# WSTL18P2.net
KiCad netlist of a schematic drawn in EAGLE
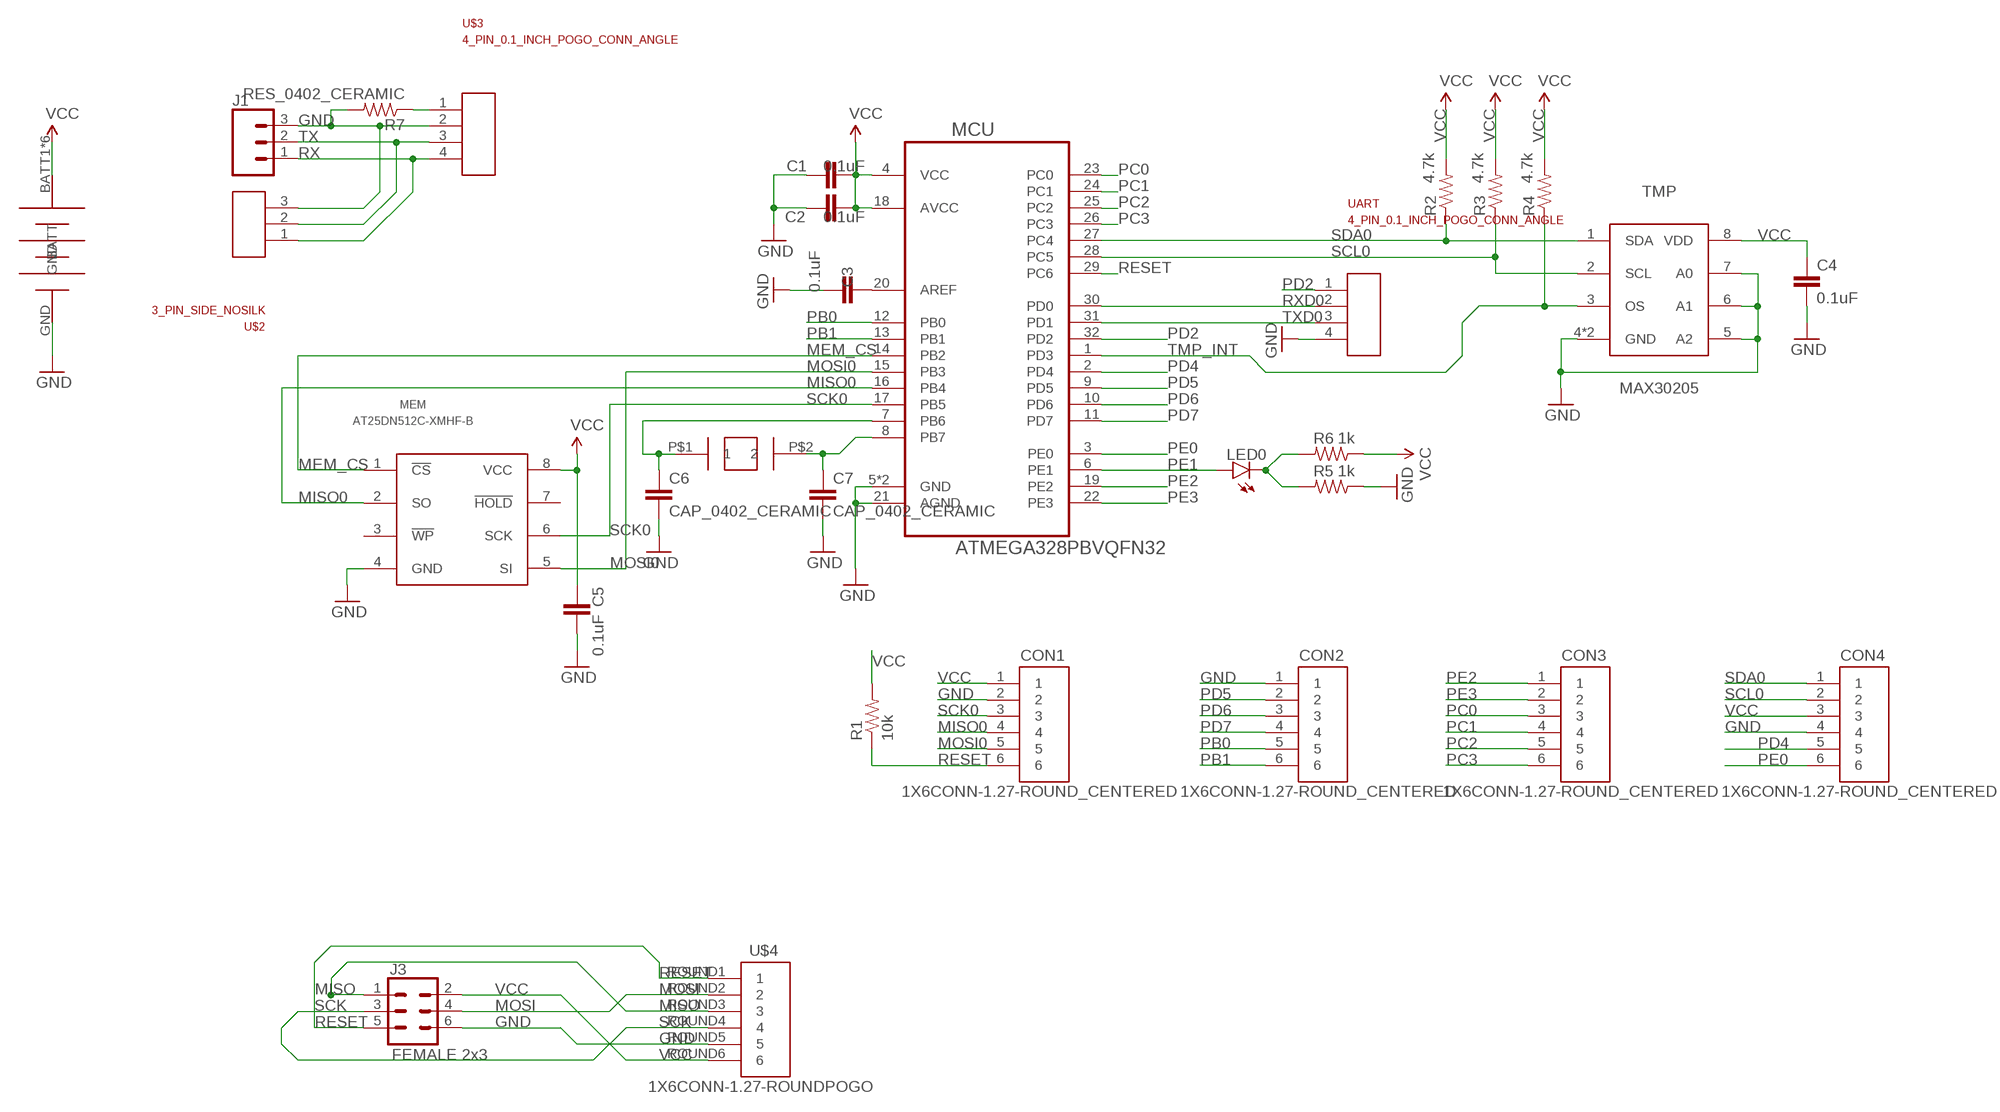
[diagram p0: schematic, sheet 1]

(export (version "E")
  (design (tool "Eeschema 10.0.6"))
  (components
    (comp (ref "C1")
      (value "0.1uF")
      (footprint "eagle-import:SMD_0402")
      (libsource (lib "eagle-import") (part "CAP_0402"))
    )
    (comp (ref "C2")
      (value "0.1uF")
      (footprint "eagle-import:SMD_0402")
      (libsource (lib "eagle-import") (part "CAP_0402"))
    )
    (comp (ref "C3")
      (value "0.1uF")
      (footprint "eagle-import:SMD_0402")
      (libsource (lib "eagle-import") (part "CAP_0402"))
    )
    (comp (ref "C4")
      (value "0.1uF")
      (footprint "eagle-import:CAP_0402")
      (libsource (lib "eagle-import") (part "CAP_0402_CERAMIC"))
    )
    (comp (ref "C5")
      (value "0.1uF")
      (footprint "eagle-import:CAP_0402")
      (libsource (lib "eagle-import") (part "CAP_0402_CERAMIC"))
    )
    (comp (ref "C6")
      (value "CAP_0402_CERAMIC")
      (footprint "eagle-import:CAP_0402")
      (libsource (lib "eagle-import") (part "CAP_0402_CERAMIC"))
    )
    (comp (ref "C7")
      (value "CAP_0402_CERAMIC")
      (footprint "eagle-import:CAP_0402")
      (libsource (lib "eagle-import") (part "CAP_0402_CERAMIC"))
    )
    (comp (ref "CON1")
      (value "1X6CONN-1.27-ROUND_CENTERED")
      (footprint "eagle-import:1X6_1.27_ROUND_CENTERED")
      (libsource (lib "eagle-import") (part "1X6CONN-1.27-ROUND_CENTERED"))
    )
    (comp (ref "CON2")
      (value "1X6CONN-1.27-ROUND_CENTERED")
      (footprint "eagle-import:1X6_1.27_ROUND_CENTERED")
      (libsource (lib "eagle-import") (part "1X6CONN-1.27-ROUND_CENTERED"))
    )
    (comp (ref "CON3")
      (value "1X6CONN-1.27-ROUND_CENTERED")
      (footprint "eagle-import:1X6_1.27_ROUND_CENTERED")
      (libsource (lib "eagle-import") (part "1X6CONN-1.27-ROUND_CENTERED"))
    )
    (comp (ref "CON4")
      (value "1X6CONN-1.27-ROUND_CENTERED")
      (footprint "eagle-import:1X6_1.27_ROUND_CENTERED")
      (libsource (lib "eagle-import") (part "1X6CONN-1.27-ROUND_CENTERED"))
    )
    (comp (ref "J1")
      (value "CONN_03")
      (footprint "eagle-import:1X03")
      (libsource (lib "eagle-import") (part "CONN_03"))
    )
    (comp (ref "J3")
      (value "FEMALE 2x3")
      (footprint "eagle-import:2X3")
      (libsource (lib "eagle-import") (part "CONN_03X2FEMALE"))
    )
    (comp (ref "LED0")
      (value "LED_0402")
      (footprint "eagle-import:LED_0402")
      (libsource (lib "eagle-import") (part "LED_0402"))
    )
    (comp (ref "MCU")
      (value "ATMEGA328PBVQFN32")
      (footprint "eagle-import:ATMEGA328PB_VFQFN32")
      (libsource (lib "eagle-import") (part "ATMEGA328PBVQFN32"))
    )
    (comp (ref "MEM")
      (value "AT25DN512C-XMHF-B")
      (footprint "eagle-import:TSSSOP-8")
      (libsource (lib "eagle-import") (part "AT25DN512C-XMHF-B"))
    )
    (comp (ref "R1")
      (value "10k")
      (footprint "eagle-import:RES_0402")
      (libsource (lib "eagle-import") (part "RES_0402_CERAMIC"))
    )
    (comp (ref "R2")
      (value "4.7k")
      (footprint "eagle-import:RES_0402")
      (libsource (lib "eagle-import") (part "RES_0402_CERAMIC"))
    )
    (comp (ref "R3")
      (value "4.7k")
      (footprint "eagle-import:RES_0402")
      (libsource (lib "eagle-import") (part "RES_0402_CERAMIC"))
    )
    (comp (ref "R4")
      (value "4.7k")
      (footprint "eagle-import:RES_0402")
      (libsource (lib "eagle-import") (part "RES_0402_CERAMIC"))
    )
    (comp (ref "R5")
      (value "1k")
      (footprint "eagle-import:RES_0402")
      (libsource (lib "eagle-import") (part "RES_0402_CERAMIC"))
    )
    (comp (ref "R6")
      (value "1k")
      (footprint "eagle-import:RES_0402")
      (libsource (lib "eagle-import") (part "RES_0402_CERAMIC"))
    )
    (comp (ref "R7")
      (value "RES_0402_CERAMIC")
      (footprint "eagle-import:RES_0402")
      (libsource (lib "eagle-import") (part "RES_0402_CERAMIC"))
    )
    (comp (ref "T1")
      (value "ABS07AIG")
      (footprint "eagle-import:ABS07AIG")
      (libsource (lib "eagle-import") (part "ABS07AIG"))
    )
    (comp (ref "TMP")
      (value "MAX30205")
      (footprint "eagle-import:MAX30205_TDFN8")
      (libsource (lib "eagle-import") (part "MAX30205"))
    )
    (comp (ref "U$1")
      (value "LINX-CR2032-BAT-HLD-M-THM")
      (footprint "eagle-import:CR2032-LINX-M-THM")
      (libsource (lib "eagle-import") (part "LINX-CR2032-BAT-HLD-M-THM"))
    )
    (comp (ref "U$2")
      (value "3_PIN_SIDE_NOSILK")
      (footprint "eagle-import:3PIN_SIDE_0.1_INCH_NOSILK")
      (libsource (lib "eagle-import") (part "3_PIN_SIDE_NOSILK"))
    )
    (comp (ref "U$3")
      (value "4_PIN_0.1_INCH_POGO_CONN_ANGLE")
      (footprint "eagle-import:4_PIN_0.1INCH_POGO_PADS_ANGLE")
      (libsource (lib "eagle-import") (part "4_PIN_0.1_INCH_POGO_CONN_ANGLE"))
    )
    (comp (ref "U$4")
      (value "1X6CONN-1.27-ROUNDPOGO")
      (footprint "eagle-import:1X6_1.27_SIDEPOGO")
      (libsource (lib "eagle-import") (part "1X6CONN-1.27-ROUNDPOGO"))
    )
    (comp (ref "UART")
      (value "4_PIN_0.1_INCH_POGO_CONN_ANGLE")
      (footprint "eagle-import:4_PIN_0.1INCH_POGO_PADS_ANGLE")
      (libsource (lib "eagle-import") (part "4_PIN_0.1_INCH_POGO_CONN_ANGLE"))
    )
  )
  (nets
    (net (code "1") (name "/MEM_CS") (class "Default")
      (node (ref "MCU") (pin "14") (pinfunction "PB2_14") (pintype "bidirectional"))
      (node (ref "MEM") (pin "1") (pinfunction "~{CS}_1") (pintype "bidirectional"))
    )
    (net (code "2") (name "/MISO") (class "Default")
      (node (ref "J3") (pin "1") (pinfunction "1_1") (pintype "bidirectional"))
      (node (ref "U$4") (pin "ROUND3") (pinfunction "3_ROUND3") (pintype "bidirectional"))
    )
    (net (code "3") (name "/MISO0") (class "Default")
      (node (ref "CON1") (pin "4") (pinfunction "4_4") (pintype "bidirectional"))
      (node (ref "MCU") (pin "16") (pinfunction "PB4_16") (pintype "bidirectional"))
      (node (ref "MEM") (pin "2") (pinfunction "SO_2") (pintype "bidirectional"))
    )
    (net (code "4") (name "/MOSI") (class "Default")
      (node (ref "J3") (pin "4") (pinfunction "4_4") (pintype "bidirectional"))
      (node (ref "U$4") (pin "ROUND2") (pinfunction "2_ROUND2") (pintype "bidirectional"))
    )
    (net (code "5") (name "/MOSI0") (class "Default")
      (node (ref "CON1") (pin "5") (pinfunction "5_5") (pintype "bidirectional"))
      (node (ref "MCU") (pin "15") (pinfunction "PB3_15") (pintype "bidirectional"))
      (node (ref "MEM") (pin "5") (pinfunction "SI_5") (pintype "bidirectional"))
    )
    (net (code "6") (name "/PB0") (class "Default")
      (node (ref "CON2") (pin "5") (pinfunction "5_5") (pintype "bidirectional"))
      (node (ref "MCU") (pin "12") (pinfunction "PB0_12") (pintype "bidirectional"))
    )
    (net (code "7") (name "/PB1") (class "Default")
      (node (ref "CON2") (pin "6") (pinfunction "6_6") (pintype "bidirectional"))
      (node (ref "MCU") (pin "13") (pinfunction "PB1_13") (pintype "bidirectional"))
    )
    (net (code "8") (name "/PC0") (class "Default")
      (node (ref "CON3") (pin "3") (pinfunction "3_3") (pintype "bidirectional"))
      (node (ref "MCU") (pin "23") (pinfunction "PC0_23") (pintype "bidirectional"))
    )
    (net (code "9") (name "/PC1") (class "Default")
      (node (ref "CON3") (pin "4") (pinfunction "4_4") (pintype "bidirectional"))
      (node (ref "MCU") (pin "24") (pinfunction "PC1_24") (pintype "bidirectional"))
    )
    (net (code "10") (name "/PC2") (class "Default")
      (node (ref "CON3") (pin "5") (pinfunction "5_5") (pintype "bidirectional"))
      (node (ref "MCU") (pin "25") (pinfunction "PC2_25") (pintype "bidirectional"))
    )
    (net (code "11") (name "/PC3") (class "Default")
      (node (ref "CON3") (pin "6") (pinfunction "6_6") (pintype "bidirectional"))
      (node (ref "MCU") (pin "26") (pinfunction "PC3_26") (pintype "bidirectional"))
    )
    (net (code "12") (name "/PD2") (class "Default")
      (node (ref "MCU") (pin "32") (pinfunction "PD2_32") (pintype "bidirectional"))
      (node (ref "UART") (pin "1") (pinfunction "1_1") (pintype "bidirectional"))
    )
    (net (code "13") (name "/PD4") (class "Default")
      (node (ref "CON4") (pin "5") (pinfunction "5_5") (pintype "bidirectional"))
      (node (ref "MCU") (pin "2") (pinfunction "PD4_2") (pintype "bidirectional"))
    )
    (net (code "14") (name "/PD5") (class "Default")
      (node (ref "CON2") (pin "2") (pinfunction "2_2") (pintype "bidirectional"))
      (node (ref "MCU") (pin "9") (pinfunction "PD5_9") (pintype "bidirectional"))
    )
    (net (code "15") (name "/PD6") (class "Default")
      (node (ref "CON2") (pin "3") (pinfunction "3_3") (pintype "bidirectional"))
      (node (ref "MCU") (pin "10") (pinfunction "PD6_10") (pintype "bidirectional"))
    )
    (net (code "16") (name "/PD7") (class "Default")
      (node (ref "CON2") (pin "4") (pinfunction "4_4") (pintype "bidirectional"))
      (node (ref "MCU") (pin "11") (pinfunction "PD7_11") (pintype "bidirectional"))
    )
    (net (code "17") (name "/PE0") (class "Default")
      (node (ref "CON4") (pin "6") (pinfunction "6_6") (pintype "bidirectional"))
      (node (ref "MCU") (pin "3") (pinfunction "PE0_3") (pintype "bidirectional"))
    )
    (net (code "18") (name "/PE1") (class "Default")
      (node (ref "LED0") (pin "ANODE") (pinfunction "A_ANODE") (pintype "passive"))
      (node (ref "MCU") (pin "6") (pinfunction "PE1_6") (pintype "bidirectional"))
    )
    (net (code "19") (name "/PE2") (class "Default")
      (node (ref "CON3") (pin "1") (pinfunction "1_1") (pintype "bidirectional"))
      (node (ref "MCU") (pin "19") (pinfunction "PE2_19") (pintype "bidirectional"))
    )
    (net (code "20") (name "/PE3") (class "Default")
      (node (ref "CON3") (pin "2") (pinfunction "2_2") (pintype "bidirectional"))
      (node (ref "MCU") (pin "22") (pinfunction "PE3_22") (pintype "bidirectional"))
    )
    (net (code "21") (name "/RESET") (class "Default")
      (node (ref "CON1") (pin "6") (pinfunction "6_6") (pintype "bidirectional"))
      (node (ref "J3") (pin "5") (pinfunction "5_5") (pintype "bidirectional"))
      (node (ref "MCU") (pin "29") (pinfunction "PC6_29") (pintype "bidirectional"))
      (node (ref "R1") (pin "2") (pinfunction "2_2") (pintype "passive"))
      (node (ref "U$4") (pin "ROUND1") (pinfunction "1_ROUND1") (pintype "bidirectional"))
    )
    (net (code "22") (name "/RX") (class "Default")
      (node (ref "J1") (pin "1") (pinfunction "1_1") (pintype "passive"))
      (node (ref "U$2") (pin "1") (pinfunction "1_1") (pintype "bidirectional"))
      (node (ref "U$3") (pin "4") (pinfunction "4_4") (pintype "bidirectional"))
    )
    (net (code "23") (name "/RXD0") (class "Default")
      (node (ref "MCU") (pin "30") (pinfunction "PD0_30") (pintype "bidirectional"))
      (node (ref "UART") (pin "2") (pinfunction "2_2") (pintype "bidirectional"))
    )
    (net (code "24") (name "/SCK") (class "Default")
      (node (ref "J3") (pin "3") (pinfunction "3_3") (pintype "bidirectional"))
      (node (ref "U$4") (pin "ROUND4") (pinfunction "4_ROUND4") (pintype "bidirectional"))
    )
    (net (code "25") (name "/SCK0") (class "Default")
      (node (ref "CON1") (pin "3") (pinfunction "3_3") (pintype "bidirectional"))
      (node (ref "MCU") (pin "17") (pinfunction "PB5_17") (pintype "bidirectional"))
      (node (ref "MEM") (pin "6") (pinfunction "SCK_6") (pintype "bidirectional"))
    )
    (net (code "26") (name "/SCL0") (class "Default")
      (node (ref "CON4") (pin "2") (pinfunction "2_2") (pintype "bidirectional"))
      (node (ref "MCU") (pin "28") (pinfunction "PC5_28") (pintype "bidirectional"))
      (node (ref "R3") (pin "2") (pinfunction "2_2") (pintype "passive"))
      (node (ref "TMP") (pin "2") (pinfunction "SCL_2") (pintype "bidirectional"))
    )
    (net (code "27") (name "/SDA0") (class "Default")
      (node (ref "CON4") (pin "1") (pinfunction "1_1") (pintype "bidirectional"))
      (node (ref "MCU") (pin "27") (pinfunction "PC4_27") (pintype "bidirectional"))
      (node (ref "R2") (pin "2") (pinfunction "2_2") (pintype "passive"))
      (node (ref "TMP") (pin "1") (pinfunction "SDA_1") (pintype "bidirectional"))
    )
    (net (code "28") (name "/TMP_INT") (class "Default")
      (node (ref "MCU") (pin "1") (pinfunction "PD3_1") (pintype "bidirectional"))
      (node (ref "R4") (pin "2") (pinfunction "2_2") (pintype "passive"))
      (node (ref "TMP") (pin "3") (pinfunction "OS_3") (pintype "bidirectional"))
    )
    (net (code "29") (name "/TX") (class "Default")
      (node (ref "J1") (pin "2") (pinfunction "2_2") (pintype "passive"))
      (node (ref "U$2") (pin "2") (pinfunction "2_2") (pintype "bidirectional"))
      (node (ref "U$3") (pin "3") (pinfunction "3_3") (pintype "bidirectional"))
    )
    (net (code "30") (name "/TXD0") (class "Default")
      (node (ref "MCU") (pin "31") (pinfunction "PD1_31") (pintype "bidirectional"))
      (node (ref "UART") (pin "3") (pinfunction "3_3") (pintype "bidirectional"))
    )
    (net (code "31") (name "GND") (class "Default")
      (node (ref "C1") (pin "2") (pinfunction "2_2") (pintype "bidirectional"))
      (node (ref "C2") (pin "2") (pinfunction "2_2") (pintype "bidirectional"))
      (node (ref "C3") (pin "2") (pinfunction "2_2") (pintype "bidirectional"))
      (node (ref "C4") (pin "2") (pinfunction "2_2") (pintype "passive"))
      (node (ref "C5") (pin "2") (pinfunction "2_2") (pintype "passive"))
      (node (ref "C6") (pin "2") (pinfunction "2_2") (pintype "passive"))
      (node (ref "C7") (pin "2") (pinfunction "2_2") (pintype "passive"))
      (node (ref "CON1") (pin "2") (pinfunction "2_2") (pintype "bidirectional"))
      (node (ref "CON2") (pin "1") (pinfunction "1_1") (pintype "bidirectional"))
      (node (ref "CON4") (pin "4") (pinfunction "4_4") (pintype "bidirectional"))
      (node (ref "J1") (pin "3") (pinfunction "3_3") (pintype "passive"))
      (node (ref "J3") (pin "6") (pinfunction "6_6") (pintype "bidirectional"))
      (node (ref "MCU") (pin "21") (pinfunction "AGND_21") (pintype "passive"))
      (node (ref "MCU") (pin "5") (pinfunction "GND_5") (pintype "passive"))
      (node (ref "MCU") (pin "PAD") (pinfunction "GND_PAD") (pintype "passive"))
      (node (ref "MEM") (pin "4") (pinfunction "GND_4") (pintype "bidirectional"))
      (node (ref "R5") (pin "2") (pinfunction "2_2") (pintype "passive"))
      (node (ref "R7") (pin "1") (pinfunction "1_1") (pintype "passive"))
      (node (ref "TMP") (pin "4") (pinfunction "GND_4") (pintype "bidirectional"))
      (node (ref "TMP") (pin "5") (pinfunction "A2_5") (pintype "bidirectional"))
      (node (ref "TMP") (pin "6") (pinfunction "A1_6") (pintype "bidirectional"))
      (node (ref "TMP") (pin "7") (pinfunction "A0_7") (pintype "bidirectional"))
      (node (ref "TMP") (pin "PAD") (pinfunction "GND_PAD") (pintype "bidirectional"))
      (node (ref "U$1") (pin "GND") (pinfunction "GND_GND") (pintype "bidirectional"))
      (node (ref "U$2") (pin "3") (pinfunction "3_3") (pintype "bidirectional"))
      (node (ref "U$3") (pin "2") (pinfunction "2_2") (pintype "bidirectional"))
      (node (ref "U$4") (pin "ROUND5") (pinfunction "5_ROUND5") (pintype "bidirectional"))
      (node (ref "UART") (pin "4") (pinfunction "4_4") (pintype "bidirectional"))
    )
    (net (code "32") (name "Net-(LED0-C)") (class "Default")
      (node (ref "LED0") (pin "CATHODE") (pinfunction "C_CATHODE") (pintype "passive"))
      (node (ref "R5") (pin "1") (pinfunction "1_1") (pintype "passive"))
      (node (ref "R6") (pin "1") (pinfunction "1_1") (pintype "passive"))
    )
    (net (code "33") (name "Net-(MCU-AREF)") (class "Default")
      (node (ref "C3") (pin "1") (pinfunction "1_1") (pintype "bidirectional"))
      (node (ref "MCU") (pin "20") (pinfunction "AREF_20") (pintype "input"))
    )
    (net (code "34") (name "Net-(MCU-PB6)") (class "Default")
      (node (ref "C6") (pin "1") (pinfunction "1_1") (pintype "passive"))
      (node (ref "MCU") (pin "7") (pinfunction "PB6_7") (pintype "bidirectional"))
      (node (ref "T1") (pin "P$1") (pinfunction "1_P$1") (pintype "bidirectional"))
    )
    (net (code "35") (name "Net-(MCU-PB7)") (class "Default")
      (node (ref "C7") (pin "1") (pinfunction "1_1") (pintype "passive"))
      (node (ref "MCU") (pin "8") (pinfunction "PB7_8") (pintype "bidirectional"))
      (node (ref "T1") (pin "P$2") (pinfunction "2_P$2") (pintype "bidirectional"))
    )
    (net (code "36") (name "Net-(R7-Pad2)") (class "Default")
      (node (ref "R7") (pin "2") (pinfunction "2_2") (pintype "passive"))
      (node (ref "U$3") (pin "1") (pinfunction "1_1") (pintype "bidirectional"))
    )
    (net (code "37") (name "VCC") (class "Default")
      (node (ref "C1") (pin "1") (pinfunction "1_1") (pintype "bidirectional"))
      (node (ref "C2") (pin "1") (pinfunction "1_1") (pintype "bidirectional"))
      (node (ref "C4") (pin "1") (pinfunction "1_1") (pintype "passive"))
      (node (ref "C5") (pin "1") (pinfunction "1_1") (pintype "passive"))
      (node (ref "CON1") (pin "1") (pinfunction "1_1") (pintype "bidirectional"))
      (node (ref "CON4") (pin "3") (pinfunction "3_3") (pintype "bidirectional"))
      (node (ref "J3") (pin "2") (pinfunction "2_2") (pintype "bidirectional"))
      (node (ref "MCU") (pin "18") (pinfunction "AVCC_18") (pintype "power_in"))
      (node (ref "MCU") (pin "4") (pinfunction "VCC_4") (pintype "power_in"))
      (node (ref "MEM") (pin "8") (pinfunction "VCC_8") (pintype "bidirectional"))
      (node (ref "R1") (pin "1") (pinfunction "1_1") (pintype "passive"))
      (node (ref "R2") (pin "1") (pinfunction "1_1") (pintype "passive"))
      (node (ref "R3") (pin "1") (pinfunction "1_1") (pintype "passive"))
      (node (ref "R4") (pin "1") (pinfunction "1_1") (pintype "passive"))
      (node (ref "R6") (pin "2") (pinfunction "2_2") (pintype "passive"))
      (node (ref "TMP") (pin "8") (pinfunction "VDD_8") (pintype "bidirectional"))
      (node (ref "U$1") (pin "BATT1") (pinfunction "BATT_BATT1") (pintype "bidirectional"))
      (node (ref "U$1") (pin "BATT2") (pinfunction "BATT_BATT2") (pintype "bidirectional"))
      (node (ref "U$1") (pin "BATT3") (pinfunction "BATT_BATT3") (pintype "bidirectional"))
      (node (ref "U$1") (pin "BATT4") (pinfunction "BATT_BATT4") (pintype "bidirectional"))
      (node (ref "U$1") (pin "BATT5") (pinfunction "BATT_BATT5") (pintype "bidirectional"))
      (node (ref "U$1") (pin "BATT6") (pinfunction "BATT_BATT6") (pintype "bidirectional"))
      (node (ref "U$4") (pin "ROUND6") (pinfunction "6_ROUND6") (pintype "bidirectional"))
    )
    (net (code "38") (name "unconnected-(MEM-~{HOLD}-Pad7)") (class "Default")
      (node (ref "MEM") (pin "7") (pinfunction "~{HOLD}_7") (pintype "bidirectional"))
    )
    (net (code "39") (name "unconnected-(MEM-~{WP}-Pad3)") (class "Default")
      (node (ref "MEM") (pin "3") (pinfunction "~{WP}_3") (pintype "bidirectional"))
    )
  )
)
